# PushButtondirection.net
KiCad netlist of a schematic drawn in Altium Designer
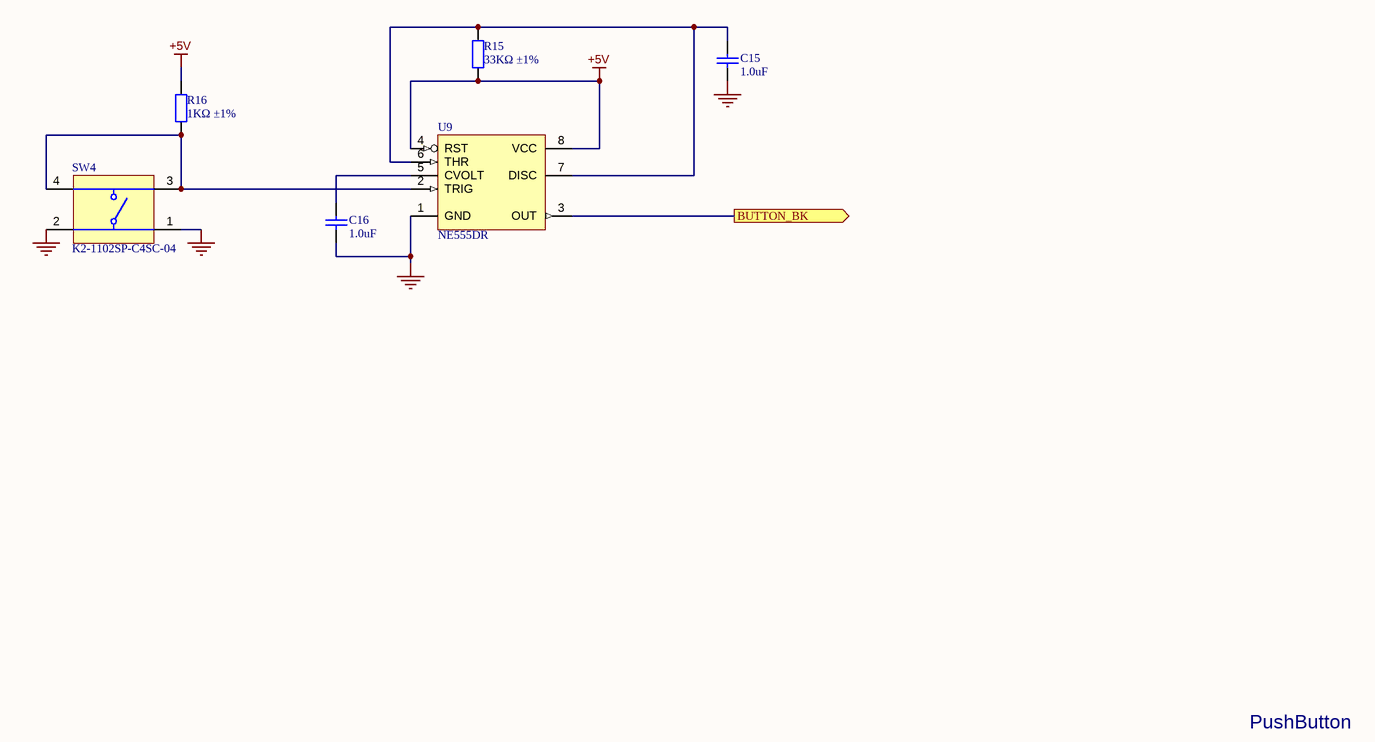
[diagram p0: PushButtondirection.SchDoc]

(export (version "E")
  (design (tool "Eeschema 10.0.6"))
  (components
    (comp (ref "C15")
      (value "1.0uF")
      (footprint "0402_C")
      (description "Chip capacitor")
      (fields
        (field (name "MANUFACTURER") "Samsung Electro-Mechanics")
        (field (name "PARTNUMBER") "CL05A105KA5NQNC")
      )
      (libsource (lib "Cap") (part "0402 1.0uF (105) 10% 25V"))
    )
    (comp (ref "C16")
      (value "1.0uF")
      (footprint "0402_C")
      (description "Chip capacitor")
      (fields
        (field (name "MANUFACTURER") "Samsung Electro-Mechanics")
        (field (name "PARTNUMBER") "CL05A105KA5NQNC")
      )
      (libsource (lib "Cap") (part "0402 1.0uF (105) 10% 25V"))
    )
    (comp (ref "R15")
      (value "33KΩ ±1%")
      (footprint "0402_R")
      (description "Chip resistor")
      (fields (field (name "MANUFACTURER") "Uniroyal Elec") (field (name "PARTNUMBER") "0402WGF3302TCE"))
      (libsource (lib "RES") (part "0402 33K (3302) 1%"))
    )
    (comp (ref "R16")
      (value "1KΩ ±1%")
      (footprint "0402_R")
      (description "Chip resistor")
      (fields (field (name "MANUFACTURER") "Uniroyal Elec") (field (name "PARTNUMBER") "0402WGF1001TCE"))
      (libsource (lib "RES") (part "0402 1K (1001) 1%"))
    )
    (comp (ref "SW4")
      (value "K2-1102SP-C4SC-04")
      (footprint "TECO-FSM4JSMATR_V")
      (description "Top Actuated 50mA @ 12VDC Round Button SPST 6*6mm Tactile Switches ROHS")
      (libsource (lib "Altium Content Vault") (part "SW-SPST-4_A"))
    )
    (comp (ref "U9")
      (value "NE555DR")
      (footprint "SOIC-8_150mil")
      (description "时基集成")
      (libsource (lib "IC") (part "NE555DR_[C7593]"))
    )
  )
  (nets
    (net (code "1") (name "+5V") (class "Default")
      (node (ref "R15") (pin "1") (pinfunction "1_1") (pintype "passive"))
      (node (ref "R16") (pin "1") (pinfunction "1_1") (pintype "passive"))
      (node (ref "U9") (pin "4") (pinfunction "RST_4") (pintype "input"))
      (node (ref "U9") (pin "8") (pinfunction "VCC_8") (pintype "power_in"))
    )
    (net (code "2") (name "/BUTTON_BK") (class "Default")
      (node (ref "U9") (pin "3") (pinfunction "OUT_3") (pintype "output"))
    )
    (net (code "3") (name "GND") (class "Default")
      (node (ref "C15") (pin "1") (pinfunction "1_1") (pintype "passive"))
      (node (ref "C16") (pin "2") (pinfunction "2_2") (pintype "passive"))
      (node (ref "SW4") (pin "1") (pinfunction "1_1") (pintype "passive"))
      (node (ref "SW4") (pin "2") (pinfunction "2_2") (pintype "passive"))
      (node (ref "U9") (pin "1") (pinfunction "GND_1") (pintype "power_in"))
    )
    (net (code "4") (name "Net-(U9-CVOLT)") (class "Default")
      (node (ref "C16") (pin "1") (pinfunction "1_1") (pintype "passive"))
      (node (ref "U9") (pin "5") (pinfunction "CVOLT_5") (pintype "passive"))
    )
    (net (code "5") (name "Net-(U9-DISC)") (class "Default")
      (node (ref "C15") (pin "2") (pinfunction "2_2") (pintype "passive"))
      (node (ref "R15") (pin "2") (pinfunction "2_2") (pintype "passive"))
      (node (ref "U9") (pin "6") (pinfunction "THR_6") (pintype "input"))
      (node (ref "U9") (pin "7") (pinfunction "DISC_7") (pintype "open_collector"))
    )
    (net (code "6") (name "Net-(U9-TRIG)") (class "Default")
      (node (ref "R16") (pin "2") (pinfunction "2_2") (pintype "passive"))
      (node (ref "SW4") (pin "3") (pinfunction "3_3") (pintype "passive"))
      (node (ref "SW4") (pin "4") (pinfunction "4_4") (pintype "passive"))
      (node (ref "U9") (pin "2") (pinfunction "TRIG_2") (pintype "input"))
    )
  )
)
